# WaterThePlants.net
KiCad netlist of a schematic drawn in EAGLE
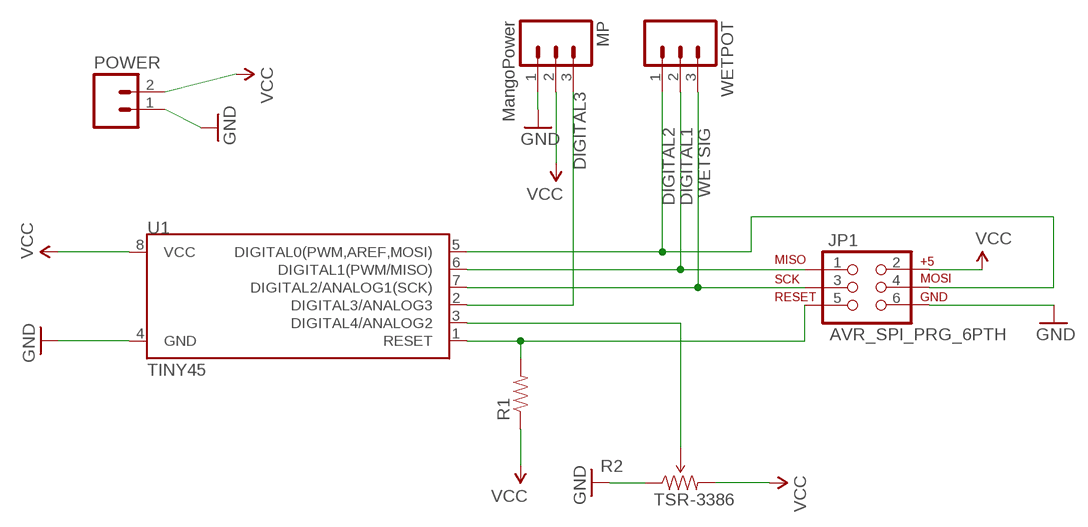
[diagram p0: schematic, sheet 1]

(export (version "E")
  (design (tool "Eeschema 10.0.6"))
  (components
    (comp (ref "JP1")
      (value "AVR_SPI_PRG_6PTH")
      (footprint "eagle-import:2X3")
      (libsource (lib "eagle-import") (part "AVR_SPI_PRG_6PTH"))
    )
    (comp (ref "MP")
      (value "MangoPower")
      (footprint "eagle-import:1X03")
      (libsource (lib "eagle-import") (part "M03PTH"))
    )
    (comp (ref "POWER")
      (value "M02POLAR")
      (footprint "eagle-import:MOLEX-1X2")
      (libsource (lib "eagle-import") (part "M02POLAR"))
    )
    (comp (ref "R1")
      (value "RESISTORAXIAL-0.3")
      (footprint "eagle-import:AXIAL-0.3")
      (libsource (lib "eagle-import") (part "RESISTORAXIAL-0.3"))
    )
    (comp (ref "R2")
      (value "TSR-3386")
      (footprint "eagle-import:3362U-2")
      (libsource (lib "eagle-import") (part "TRIMPOT3362U-2"))
    )
    (comp (ref "U1")
      (value "TINY45")
      (footprint "eagle-import:DIP08")
      (libsource (lib "eagle-import") (part "ARDUINO-ATTINY45/85TINY45-20-DIP"))
    )
    (comp (ref "WETPOT")
      (value "M03PTH")
      (footprint "eagle-import:1X03")
      (libsource (lib "eagle-import") (part "M03PTH"))
    )
  )
  (nets
    (net (code "1") (name "/DIGITAL1") (class "Default")
      (node (ref "JP1") (pin "1") (pinfunction "1_1") (pintype "passive"))
      (node (ref "U1") (pin "6") (pinfunction "DIGITAL1(PWM/MISO)_6") (pintype "bidirectional"))
      (node (ref "WETPOT") (pin "2") (pinfunction "2_2") (pintype "passive"))
    )
    (net (code "2") (name "/DIGITAL2") (class "Default")
      (node (ref "JP1") (pin "4") (pinfunction "4_4") (pintype "passive"))
      (node (ref "U1") (pin "5") (pinfunction "DIGITAL0(PWM,AREF,MOSI)_5") (pintype "bidirectional"))
      (node (ref "WETPOT") (pin "1") (pinfunction "1_1") (pintype "passive"))
    )
    (net (code "3") (name "/DIGITAL3") (class "Default")
      (node (ref "MP") (pin "3") (pinfunction "3_3") (pintype "passive"))
      (node (ref "U1") (pin "2") (pinfunction "DIGITAL3/ANALOG3_2") (pintype "bidirectional"))
    )
    (net (code "4") (name "/WETSIG") (class "Default")
      (node (ref "JP1") (pin "3") (pinfunction "3_3") (pintype "passive"))
      (node (ref "U1") (pin "7") (pinfunction "DIGITAL2/ANALOG1(SCK)_7") (pintype "bidirectional"))
      (node (ref "WETPOT") (pin "3") (pinfunction "3_3") (pintype "passive"))
    )
    (net (code "5") (name "GND") (class "Default")
      (node (ref "JP1") (pin "6") (pinfunction "6_6") (pintype "passive"))
      (node (ref "MP") (pin "1") (pinfunction "1_1") (pintype "passive"))
      (node (ref "POWER") (pin "1") (pinfunction "1_1") (pintype "passive"))
      (node (ref "R2") (pin "1") (pinfunction "CCW_1") (pintype "passive"))
      (node (ref "U1") (pin "4") (pinfunction "GND_4") (pintype "bidirectional"))
    )
    (net (code "6") (name "Net-(R1-2)") (class "Default")
      (node (ref "JP1") (pin "5") (pinfunction "5_5") (pintype "passive"))
      (node (ref "R1") (pin "P$2") (pinfunction "2_P$2") (pintype "passive"))
      (node (ref "U1") (pin "1") (pinfunction "RESET_1") (pintype "bidirectional"))
    )
    (net (code "7") (name "Net-(R2-WIPER)") (class "Default")
      (node (ref "R2") (pin "2") (pinfunction "WIPER_2") (pintype "passive"))
      (node (ref "U1") (pin "3") (pinfunction "DIGITAL4/ANALOG2_3") (pintype "bidirectional"))
    )
    (net (code "8") (name "VCC") (class "Default")
      (node (ref "JP1") (pin "2") (pinfunction "2_2") (pintype "passive"))
      (node (ref "MP") (pin "2") (pinfunction "2_2") (pintype "passive"))
      (node (ref "POWER") (pin "2") (pinfunction "2_2") (pintype "passive"))
      (node (ref "R1") (pin "P$1") (pinfunction "1_P$1") (pintype "passive"))
      (node (ref "R2") (pin "3") (pinfunction "CW_3") (pintype "passive"))
      (node (ref "U1") (pin "8") (pinfunction "VCC_8") (pintype "bidirectional"))
    )
  )
)
